# ROL2-B1-P02.net
KiCad netlist of a schematic drawn in Altium Designer
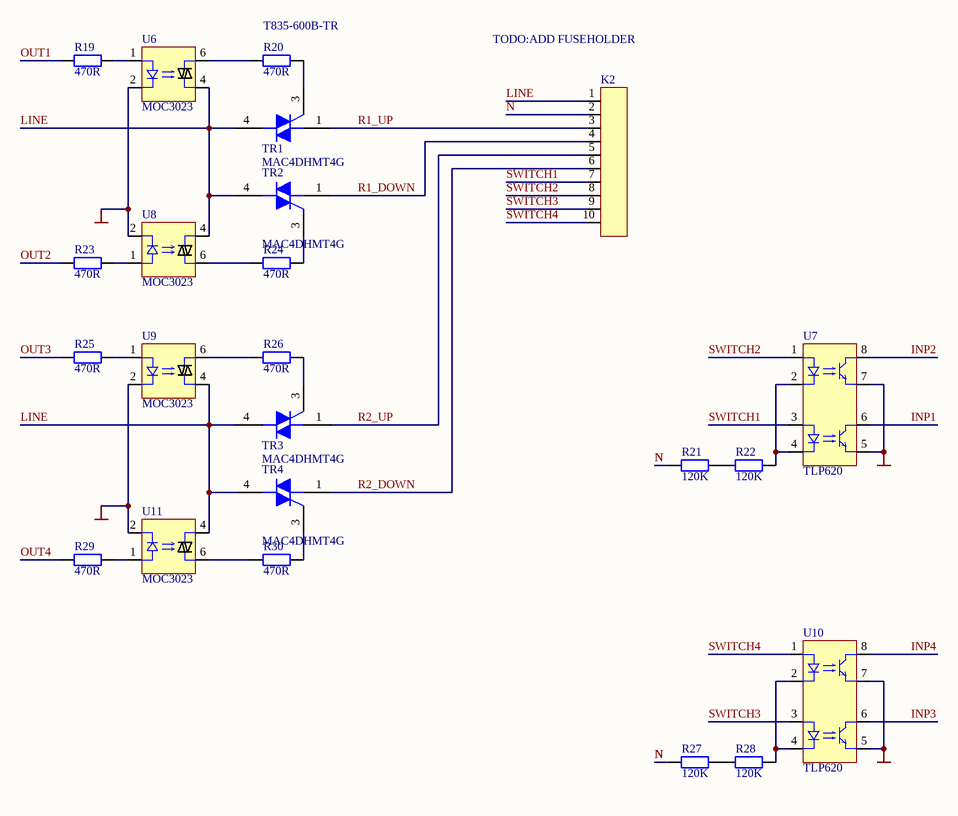
[diagram p0: ROL2-B1-P02.SchDoc]

(export (version "E")
  (design (tool "Eeschema 10.0.6"))
  (components
    (comp (ref "K2")
      (value "Terminal Block Connector, 3.81mm, Right Angle")
      (footprint "CONN_3.81_10")
      (description "Terminal Block Connector, 3.81mm, 8pin")
      (libsource (lib "fractal_lib") (part "CONN_TB_3.81_10PIN"))
    )
    (comp (ref "R19")
      (value "470R")
      (footprint "RC0805-1")
      (description "Chip Resistor 0805")
      (libsource (lib "Resistors") (part "RES0805"))
    )
    (comp (ref "R20")
      (value "470R")
      (footprint "RC0805-1")
      (description "Chip Resistor 0805")
      (libsource (lib "Resistors") (part "RES0805"))
    )
    (comp (ref "R21")
      (value "120K")
      (footprint "RC1206-1")
      (description "Chip Resistor 1206")
      (libsource (lib "Resistors") (part "RES1206"))
    )
    (comp (ref "R22")
      (value "120K")
      (footprint "RC1206-1")
      (description "Chip Resistor 1206")
      (libsource (lib "Resistors") (part "RES1206"))
    )
    (comp (ref "R23")
      (value "470R")
      (footprint "RC0805-1")
      (description "Chip Resistor 0805")
      (libsource (lib "Resistors") (part "RES0805"))
    )
    (comp (ref "R24")
      (value "470R")
      (footprint "RC0805-1")
      (description "Chip Resistor 0805")
      (libsource (lib "") (part "RES0805_1"))
    )
    (comp (ref "R25")
      (value "470R")
      (footprint "RC0805-1")
      (description "Chip Resistor 0805")
      (libsource (lib "Resistors") (part "RES0805"))
    )
    (comp (ref "R26")
      (value "470R")
      (footprint "RC0805-1")
      (description "Chip Resistor 0805")
      (libsource (lib "Resistors") (part "RES0805"))
    )
    (comp (ref "R27")
      (value "120K")
      (footprint "RC1206-1")
      (description "Chip Resistor 1206")
      (libsource (lib "Resistors") (part "RES1206"))
    )
    (comp (ref "R28")
      (value "120K")
      (footprint "RC1206-1")
      (description "Chip Resistor 1206")
      (libsource (lib "Resistors") (part "RES1206"))
    )
    (comp (ref "R29")
      (value "470R")
      (footprint "RC0805-1")
      (description "Chip Resistor 0805")
      (libsource (lib "Resistors") (part "RES0805"))
    )
    (comp (ref "R30")
      (value "470R")
      (footprint "RC0805-1")
      (description "Chip Resistor 0805")
      (libsource (lib "") (part "RES0805_1"))
    )
    (comp (ref "TR1")
      (value "MAC4DHMT4G")
      (footprint "ONSC-DPAK-3-369C-01_V")
      (description "Sensitive Gate Triacs, 3-Pin DPAK, Pb-Free, Tape and Reel")
      (fields (field (name "MANUFACTURER") "On Semiconductor"))
      (libsource (lib "fractal_lib") (part "MAC4DHMT4G"))
    )
    (comp (ref "TR2")
      (value "MAC4DHMT4G")
      (footprint "ONSC-DPAK-3-369C-01_V")
      (description "Sensitive Gate Triacs, 3-Pin DPAK, Pb-Free, Tape and Reel")
      (fields (field (name "MANUFACTURER") "On Semiconductor"))
      (libsource (lib "fractal_lib") (part "MAC4DHMT4G"))
    )
    (comp (ref "TR3")
      (value "MAC4DHMT4G")
      (footprint "ONSC-DPAK-3-369C-01_V")
      (description "Sensitive Gate Triacs, 3-Pin DPAK, Pb-Free, Tape and Reel")
      (fields (field (name "MANUFACTURER") "On Semiconductor"))
      (libsource (lib "fractal_lib") (part "MAC4DHMT4G"))
    )
    (comp (ref "TR4")
      (value "MAC4DHMT4G")
      (footprint "ONSC-DPAK-3-369C-01_V")
      (description "Sensitive Gate Triacs, 3-Pin DPAK, Pb-Free, Tape and Reel")
      (fields (field (name "MANUFACTURER") "On Semiconductor"))
      (libsource (lib "fractal_lib") (part "MAC4DHMT4G"))
    )
    (comp (ref "U6")
      (value "MOC3023")
      (footprint "DIP6")
      (description "digital temperature sensor")
      (libsource (lib "fractal_lib") (part "MOC3023"))
    )
    (comp (ref "U7")
      (value "TLP620")
      (footprint "DIP8")
      (description "digital temperature sensor")
      (libsource (lib "fractal_lib") (part "TLP620"))
    )
    (comp (ref "U8")
      (value "MOC3023")
      (footprint "DIP6")
      (description "digital temperature sensor")
      (libsource (lib "") (part "MOC3023_1"))
    )
    (comp (ref "U9")
      (value "MOC3023")
      (footprint "DIP6")
      (description "digital temperature sensor")
      (libsource (lib "fractal_lib") (part "MOC3023"))
    )
    (comp (ref "U10")
      (value "TLP620")
      (footprint "DIP8")
      (description "digital temperature sensor")
      (libsource (lib "fractal_lib") (part "TLP620"))
    )
    (comp (ref "U11")
      (value "MOC3023")
      (footprint "DIP6")
      (description "digital temperature sensor")
      (libsource (lib "") (part "MOC3023_1"))
    )
  )
  (nets
    (net (code "1") (name "/INP1") (class "Default")
      (node (ref "U7") (pin "6") (pinfunction "C_6") (pintype "passive"))
    )
    (net (code "2") (name "/INP2") (class "Default")
      (node (ref "U7") (pin "8") (pinfunction "C_8") (pintype "passive"))
    )
    (net (code "3") (name "/INP3") (class "Default")
      (node (ref "U10") (pin "6") (pinfunction "C_6") (pintype "passive"))
    )
    (net (code "4") (name "/INP4") (class "Default")
      (node (ref "U10") (pin "8") (pinfunction "C_8") (pintype "passive"))
    )
    (net (code "5") (name "/LINE") (class "Default")
      (node (ref "K2") (pin "1") (pinfunction "A_1") (pintype "passive"))
      (node (ref "TR1") (pin "4") (pinfunction "MT2_4") (pintype "passive"))
      (node (ref "TR2") (pin "4") (pinfunction "MT2_4") (pintype "passive"))
      (node (ref "TR3") (pin "4") (pinfunction "MT2_4") (pintype "passive"))
      (node (ref "TR4") (pin "4") (pinfunction "MT2_4") (pintype "passive"))
      (node (ref "U11") (pin "4") (pinfunction "E_4") (pintype "passive"))
      (node (ref "U6") (pin "4") (pinfunction "E_4") (pintype "passive"))
      (node (ref "U8") (pin "4") (pinfunction "E_4") (pintype "passive"))
      (node (ref "U9") (pin "4") (pinfunction "E_4") (pintype "passive"))
    )
    (net (code "6") (name "/N") (class "Default")
      (node (ref "K2") (pin "2") (pinfunction "K_2") (pintype "passive"))
      (node (ref "R21") (pin "1") (pinfunction "1_1") (pintype "passive"))
      (node (ref "R27") (pin "1") (pinfunction "1_1") (pintype "passive"))
    )
    (net (code "7") (name "/OUT1") (class "Default")
      (node (ref "R19") (pin "2") (pinfunction "2_2") (pintype "passive"))
    )
    (net (code "8") (name "/OUT2") (class "Default")
      (node (ref "R23") (pin "2") (pinfunction "2_2") (pintype "passive"))
    )
    (net (code "9") (name "/OUT3") (class "Default")
      (node (ref "R25") (pin "2") (pinfunction "2_2") (pintype "passive"))
    )
    (net (code "10") (name "/OUT4") (class "Default")
      (node (ref "R29") (pin "2") (pinfunction "2_2") (pintype "passive"))
    )
    (net (code "11") (name "/R1_DOWN") (class "Default")
      (node (ref "K2") (pin "4") (pinfunction "K_4") (pintype "passive"))
      (node (ref "TR2") (pin "1") (pinfunction "MT1_1") (pintype "passive"))
    )
    (net (code "12") (name "/R1_UP") (class "Default")
      (node (ref "K2") (pin "3") (pinfunction "A_3") (pintype "passive"))
      (node (ref "TR1") (pin "1") (pinfunction "MT1_1") (pintype "passive"))
    )
    (net (code "13") (name "/R2_DOWN") (class "Default")
      (node (ref "K2") (pin "6") (pinfunction "C_6") (pintype "passive"))
      (node (ref "TR4") (pin "1") (pinfunction "MT1_1") (pintype "passive"))
    )
    (net (code "14") (name "/R2_UP") (class "Default")
      (node (ref "K2") (pin "5") (pinfunction "E_5") (pintype "passive"))
      (node (ref "TR3") (pin "1") (pinfunction "MT1_1") (pintype "passive"))
    )
    (net (code "15") (name "/SWITCH1") (class "Default")
      (node (ref "K2") (pin "7") (pinfunction "E_7") (pintype "passive"))
      (node (ref "U7") (pin "3") (pinfunction "A_3") (pintype "passive"))
    )
    (net (code "16") (name "/SWITCH2") (class "Default")
      (node (ref "K2") (pin "8") (pinfunction "C_8") (pintype "passive"))
      (node (ref "U7") (pin "1") (pinfunction "A_1") (pintype "passive"))
    )
    (net (code "17") (name "/SWITCH3") (class "Default")
      (node (ref "K2") (pin "9") (pinfunction "C_9") (pintype "passive"))
      (node (ref "U10") (pin "3") (pinfunction "A_3") (pintype "passive"))
    )
    (net (code "18") (name "/SWITCH4") (class "Default")
      (node (ref "K2") (pin "10") (pinfunction "C_10") (pintype "passive"))
      (node (ref "U10") (pin "1") (pinfunction "A_1") (pintype "passive"))
    )
    (net (code "19") (name "GND") (class "Default")
      (node (ref "U10") (pin "5") (pinfunction "E_5") (pintype "passive"))
      (node (ref "U10") (pin "7") (pinfunction "E_7") (pintype "passive"))
      (node (ref "U11") (pin "2") (pinfunction "K_2") (pintype "passive"))
      (node (ref "U6") (pin "2") (pinfunction "K_2") (pintype "passive"))
      (node (ref "U7") (pin "5") (pinfunction "E_5") (pintype "passive"))
      (node (ref "U7") (pin "7") (pinfunction "E_7") (pintype "passive"))
      (node (ref "U8") (pin "2") (pinfunction "K_2") (pintype "passive"))
      (node (ref "U9") (pin "2") (pinfunction "K_2") (pintype "passive"))
    )
    (net (code "20") (name "Net-(R21-Pad2)") (class "Default")
      (node (ref "R21") (pin "2") (pinfunction "2_2") (pintype "passive"))
      (node (ref "R22") (pin "1") (pinfunction "1_1") (pintype "passive"))
    )
    (net (code "21") (name "Net-(R22-Pad2)") (class "Default")
      (node (ref "R22") (pin "2") (pinfunction "2_2") (pintype "passive"))
      (node (ref "U7") (pin "2") (pinfunction "K_2") (pintype "passive"))
      (node (ref "U7") (pin "4") (pinfunction "K_4") (pintype "passive"))
    )
    (net (code "22") (name "Net-(R27-Pad2)") (class "Default")
      (node (ref "R27") (pin "2") (pinfunction "2_2") (pintype "passive"))
      (node (ref "R28") (pin "1") (pinfunction "1_1") (pintype "passive"))
    )
    (net (code "23") (name "Net-(R28-Pad2)") (class "Default")
      (node (ref "R28") (pin "2") (pinfunction "2_2") (pintype "passive"))
      (node (ref "U10") (pin "2") (pinfunction "K_2") (pintype "passive"))
      (node (ref "U10") (pin "4") (pinfunction "K_4") (pintype "passive"))
    )
    (net (code "24") (name "Net-(TR1-G)") (class "Default")
      (node (ref "R20") (pin "1") (pinfunction "1_1") (pintype "passive"))
      (node (ref "TR1") (pin "3") (pinfunction "G_3") (pintype "passive"))
    )
    (net (code "25") (name "Net-(TR2-G)") (class "Default")
      (node (ref "R24") (pin "1") (pinfunction "1_1") (pintype "passive"))
      (node (ref "TR2") (pin "3") (pinfunction "G_3") (pintype "passive"))
    )
    (net (code "26") (name "Net-(TR3-G)") (class "Default")
      (node (ref "R26") (pin "1") (pinfunction "1_1") (pintype "passive"))
      (node (ref "TR3") (pin "3") (pinfunction "G_3") (pintype "passive"))
    )
    (net (code "27") (name "Net-(TR4-G)") (class "Default")
      (node (ref "R30") (pin "1") (pinfunction "1_1") (pintype "passive"))
      (node (ref "TR4") (pin "3") (pinfunction "G_3") (pintype "passive"))
    )
    (net (code "28") (name "Net-(U6-A)") (class "Default")
      (node (ref "R19") (pin "1") (pinfunction "1_1") (pintype "passive"))
      (node (ref "U6") (pin "1") (pinfunction "A_1") (pintype "passive"))
    )
    (net (code "29") (name "Net-(U6-C)") (class "Default")
      (node (ref "R20") (pin "2") (pinfunction "2_2") (pintype "passive"))
      (node (ref "U6") (pin "6") (pinfunction "C_6") (pintype "passive"))
    )
    (net (code "30") (name "Net-(U8-A)") (class "Default")
      (node (ref "R23") (pin "1") (pinfunction "1_1") (pintype "passive"))
      (node (ref "U8") (pin "1") (pinfunction "A_1") (pintype "passive"))
    )
    (net (code "31") (name "Net-(U8-C)") (class "Default")
      (node (ref "R24") (pin "2") (pinfunction "2_2") (pintype "passive"))
      (node (ref "U8") (pin "6") (pinfunction "C_6") (pintype "passive"))
    )
    (net (code "32") (name "Net-(U9-A)") (class "Default")
      (node (ref "R25") (pin "1") (pinfunction "1_1") (pintype "passive"))
      (node (ref "U9") (pin "1") (pinfunction "A_1") (pintype "passive"))
    )
    (net (code "33") (name "Net-(U9-C)") (class "Default")
      (node (ref "R26") (pin "2") (pinfunction "2_2") (pintype "passive"))
      (node (ref "U9") (pin "6") (pinfunction "C_6") (pintype "passive"))
    )
    (net (code "34") (name "Net-(U11-A)") (class "Default")
      (node (ref "R29") (pin "1") (pinfunction "1_1") (pintype "passive"))
      (node (ref "U11") (pin "1") (pinfunction "A_1") (pintype "passive"))
    )
    (net (code "35") (name "Net-(U11-C)") (class "Default")
      (node (ref "R30") (pin "2") (pinfunction "2_2") (pintype "passive"))
      (node (ref "U11") (pin "6") (pinfunction "C_6") (pintype "passive"))
    )
  )
)
